# ANALOG.net
KiCad netlist of a schematic drawn in Altium Designer
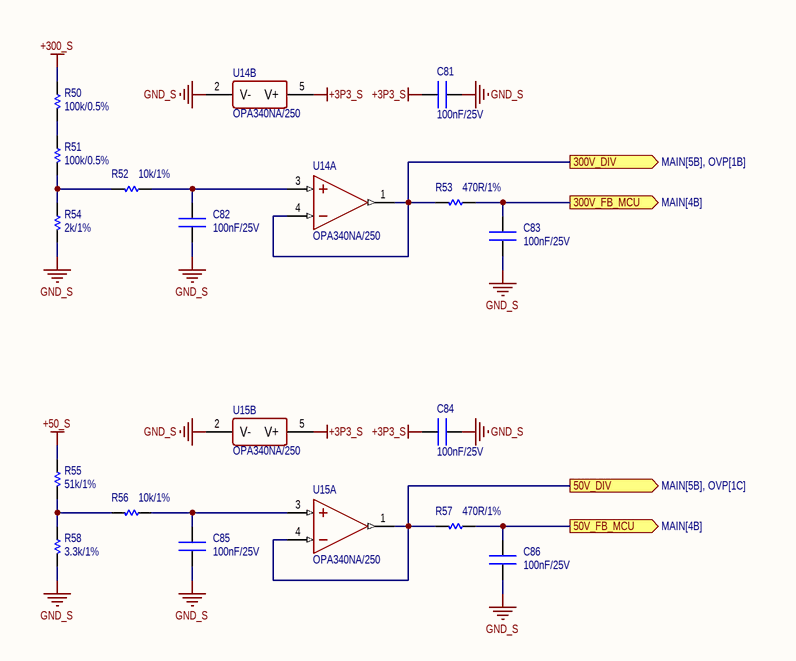
[diagram p0: ANALOG.SchDoc]

(export (version "E")
  (design (tool "Eeschema 10.0.6"))
  (components
    (comp (ref "C81")
      (value "100nF/25V")
      (footprint "CN-SMD-0603")
      (description "CAP CER 0.1UF 25V X7R 0603")
      (libsource (lib "Library") (part "CN"))
    )
    (comp (ref "C82")
      (value "100nF/25V")
      (footprint "CN-SMD-0603")
      (description "CAP CER 0.1UF 25V X7R 0603")
      (libsource (lib "Library") (part "CN"))
    )
    (comp (ref "C83")
      (value "100nF/25V")
      (footprint "CN-SMD-0603")
      (description "CAP CER 0.1UF 25V X7R 0603")
      (libsource (lib "Library") (part "CN"))
    )
    (comp (ref "C84")
      (value "100nF/25V")
      (footprint "CN-SMD-0603")
      (description "CAP CER 0.1UF 25V X7R 0603")
      (libsource (lib "Library") (part "CN"))
    )
    (comp (ref "C85")
      (value "100nF/25V")
      (footprint "CN-SMD-0603")
      (description "CAP CER 0.1UF 25V X7R 0603")
      (libsource (lib "Library") (part "CN"))
    )
    (comp (ref "C86")
      (value "100nF/25V")
      (footprint "CN-SMD-0603")
      (description "CAP CER 0.1UF 25V X7R 0603")
      (libsource (lib "Library") (part "CN"))
    )
    (comp (ref "R50")
      (value "100k/0.5%")
      (footprint "RES-SMD-2010")
      (description "RES SMD 100K OHM 5% 1/2W 2010")
      (fields
        (field (name "MANUFACTURER") "Generic Components")
        (field (name "PUBLISHER") "Altium Hobart Technology Centre")
      )
      (libsource (lib "Library") (part "Res-SMD"))
    )
    (comp (ref "R51")
      (value "100k/0.5%")
      (footprint "RES-SMD-2010")
      (description "RES SMD 100K OHM 5% 1/2W 2010")
      (fields
        (field (name "MANUFACTURER") "Generic Components")
        (field (name "PUBLISHER") "Altium Hobart Technology Centre")
      )
      (libsource (lib "Library") (part "Res-SMD"))
    )
    (comp (ref "R52")
      (value "10k/1%")
      (footprint "RES-SMD-0603")
      (description "RES SMD 10K OHM 1% 1/10W 0603")
      (fields
        (field (name "MANUFACTURER") "Generic Components")
        (field (name "PUBLISHER") "Altium Hobart Technology Centre")
      )
      (libsource (lib "Library") (part "Res-SMD"))
    )
    (comp (ref "R53")
      (value "470R/1%")
      (footprint "RES-SMD-0603")
      (description "RES 470 OHM 1% 1/10W 0603")
      (fields
        (field (name "MANUFACTURER") "Generic Components")
        (field (name "PUBLISHER") "Altium Hobart Technology Centre")
      )
      (libsource (lib "Library") (part "Res-SMD"))
    )
    (comp (ref "R54")
      (value "2k/1%")
      (footprint "RES-SMD-0603")
      (description "RES SMD 2K OHM 1% 1/10W 0603")
      (fields
        (field (name "MANUFACTURER") "Generic Components")
        (field (name "PUBLISHER") "Altium Hobart Technology Centre")
      )
      (libsource (lib "Library") (part "Res-SMD"))
    )
    (comp (ref "R55")
      (value "51k/1%")
      (footprint "RES-SMD-0603")
      (description "RES 51K OHM 1% 1/10W 0603")
      (fields
        (field (name "MANUFACTURER") "Generic Components")
        (field (name "PUBLISHER") "Altium Hobart Technology Centre")
      )
      (libsource (lib "Library") (part "Res-SMD"))
    )
    (comp (ref "R56")
      (value "10k/1%")
      (footprint "RES-SMD-0603")
      (description "RES SMD 10K OHM 1% 1/10W 0603")
      (fields
        (field (name "MANUFACTURER") "Generic Components")
        (field (name "PUBLISHER") "Altium Hobart Technology Centre")
      )
      (libsource (lib "Library") (part "Res-SMD"))
    )
    (comp (ref "R57")
      (value "470R/1%")
      (footprint "RES-SMD-0603")
      (description "RES 470 OHM 1% 1/10W 0603")
      (fields
        (field (name "MANUFACTURER") "Generic Components")
        (field (name "PUBLISHER") "Altium Hobart Technology Centre")
      )
      (libsource (lib "Library") (part "Res-SMD"))
    )
    (comp (ref "R58")
      (value "3.3k/1%")
      (footprint "RES-SMD-0603")
      (description "RES SMD 3K3 OHM 0.1% 1/10W 0603")
      (fields
        (field (name "MANUFACTURER") "Generic Components")
        (field (name "PUBLISHER") "Altium Hobart Technology Centre")
      )
      (libsource (lib "Library") (part "Res-SMD"))
    )
    (comp (ref "U14")
      (value "OPA340NA/250")
      (footprint "SOT23-5")
      (description "IC OPAMP GP 1 CIRCUIT SOT23-5")
      (libsource (lib "Library") (part "OPA340DBV"))
    )
    (comp (ref "U15")
      (value "OPA340NA/250")
      (footprint "SOT23-5")
      (description "IC OPAMP GP 1 CIRCUIT SOT23-5")
      (libsource (lib "Library") (part "OPA340DBV"))
    )
  )
  (nets
    (net (code "1") (name "+3P3_S") (class "Default")
      (node (ref "C81") (pin "1") (pinfunction "1_1") (pintype "passive"))
      (node (ref "C84") (pin "1") (pinfunction "1_1") (pintype "passive"))
      (node (ref "U14") (pin "5") (pinfunction "V+_5") (pintype "passive"))
      (node (ref "U15") (pin "5") (pinfunction "V+_5") (pintype "passive"))
    )
    (net (code "2") (name "+50_S") (class "Default")
      (node (ref "R55") (pin "1") (pinfunction "1_1") (pintype "passive"))
    )
    (net (code "3") (name "+300_S") (class "Default")
      (node (ref "R50") (pin "1") (pinfunction "1_1") (pintype "passive"))
    )
    (net (code "4") (name "/50V_DIV") (class "Default")
      (node (ref "R57") (pin "2") (pinfunction "2_2") (pintype "passive"))
      (node (ref "U15") (pin "1") (pinfunction "OUT_1") (pintype "output"))
      (node (ref "U15") (pin "4") (pinfunction "IN-_4") (pintype "input"))
    )
    (net (code "5") (name "/50V_FB_MCU") (class "Default")
      (node (ref "C86") (pin "1") (pinfunction "1_1") (pintype "passive"))
      (node (ref "R57") (pin "1") (pinfunction "1_1") (pintype "passive"))
    )
    (net (code "6") (name "/300V_DIV") (class "Default")
      (node (ref "R53") (pin "2") (pinfunction "2_2") (pintype "passive"))
      (node (ref "U14") (pin "1") (pinfunction "OUT_1") (pintype "output"))
      (node (ref "U14") (pin "4") (pinfunction "IN-_4") (pintype "input"))
    )
    (net (code "7") (name "/300V_FB_MCU") (class "Default")
      (node (ref "C83") (pin "1") (pinfunction "1_1") (pintype "passive"))
      (node (ref "R53") (pin "1") (pinfunction "1_1") (pintype "passive"))
    )
    (net (code "8") (name "GND_S") (class "Default")
      (node (ref "C81") (pin "2") (pinfunction "2_2") (pintype "passive"))
      (node (ref "C82") (pin "2") (pinfunction "2_2") (pintype "passive"))
      (node (ref "C83") (pin "2") (pinfunction "2_2") (pintype "passive"))
      (node (ref "C84") (pin "2") (pinfunction "2_2") (pintype "passive"))
      (node (ref "C85") (pin "2") (pinfunction "2_2") (pintype "passive"))
      (node (ref "C86") (pin "2") (pinfunction "2_2") (pintype "passive"))
      (node (ref "R54") (pin "2") (pinfunction "2_2") (pintype "passive"))
      (node (ref "R58") (pin "2") (pinfunction "2_2") (pintype "passive"))
      (node (ref "U14") (pin "2") (pinfunction "V-_2") (pintype "passive"))
      (node (ref "U15") (pin "2") (pinfunction "V-_2") (pintype "passive"))
    )
    (net (code "9") (name "Net-(R50-Pad2)") (class "Default")
      (node (ref "R50") (pin "2") (pinfunction "2_2") (pintype "passive"))
      (node (ref "R51") (pin "1") (pinfunction "1_1") (pintype "passive"))
    )
    (net (code "10") (name "Net-(R51-Pad2)") (class "Default")
      (node (ref "R51") (pin "2") (pinfunction "2_2") (pintype "passive"))
      (node (ref "R52") (pin "2") (pinfunction "2_2") (pintype "passive"))
      (node (ref "R54") (pin "1") (pinfunction "1_1") (pintype "passive"))
    )
    (net (code "11") (name "Net-(R55-Pad2)") (class "Default")
      (node (ref "R55") (pin "2") (pinfunction "2_2") (pintype "passive"))
      (node (ref "R56") (pin "2") (pinfunction "2_2") (pintype "passive"))
      (node (ref "R58") (pin "1") (pinfunction "1_1") (pintype "passive"))
    )
    (net (code "12") (name "Net-(U14A-IN+)") (class "Default")
      (node (ref "C82") (pin "1") (pinfunction "1_1") (pintype "passive"))
      (node (ref "R52") (pin "1") (pinfunction "1_1") (pintype "passive"))
      (node (ref "U14") (pin "3") (pinfunction "IN+_3") (pintype "input"))
    )
    (net (code "13") (name "Net-(U15A-IN+)") (class "Default")
      (node (ref "C85") (pin "1") (pinfunction "1_1") (pintype "passive"))
      (node (ref "R56") (pin "1") (pinfunction "1_1") (pintype "passive"))
      (node (ref "U15") (pin "3") (pinfunction "IN+_3") (pintype "input"))
    )
  )
)
